# Supply_Sampler.net
KiCad netlist of a schematic drawn in Altium Designer
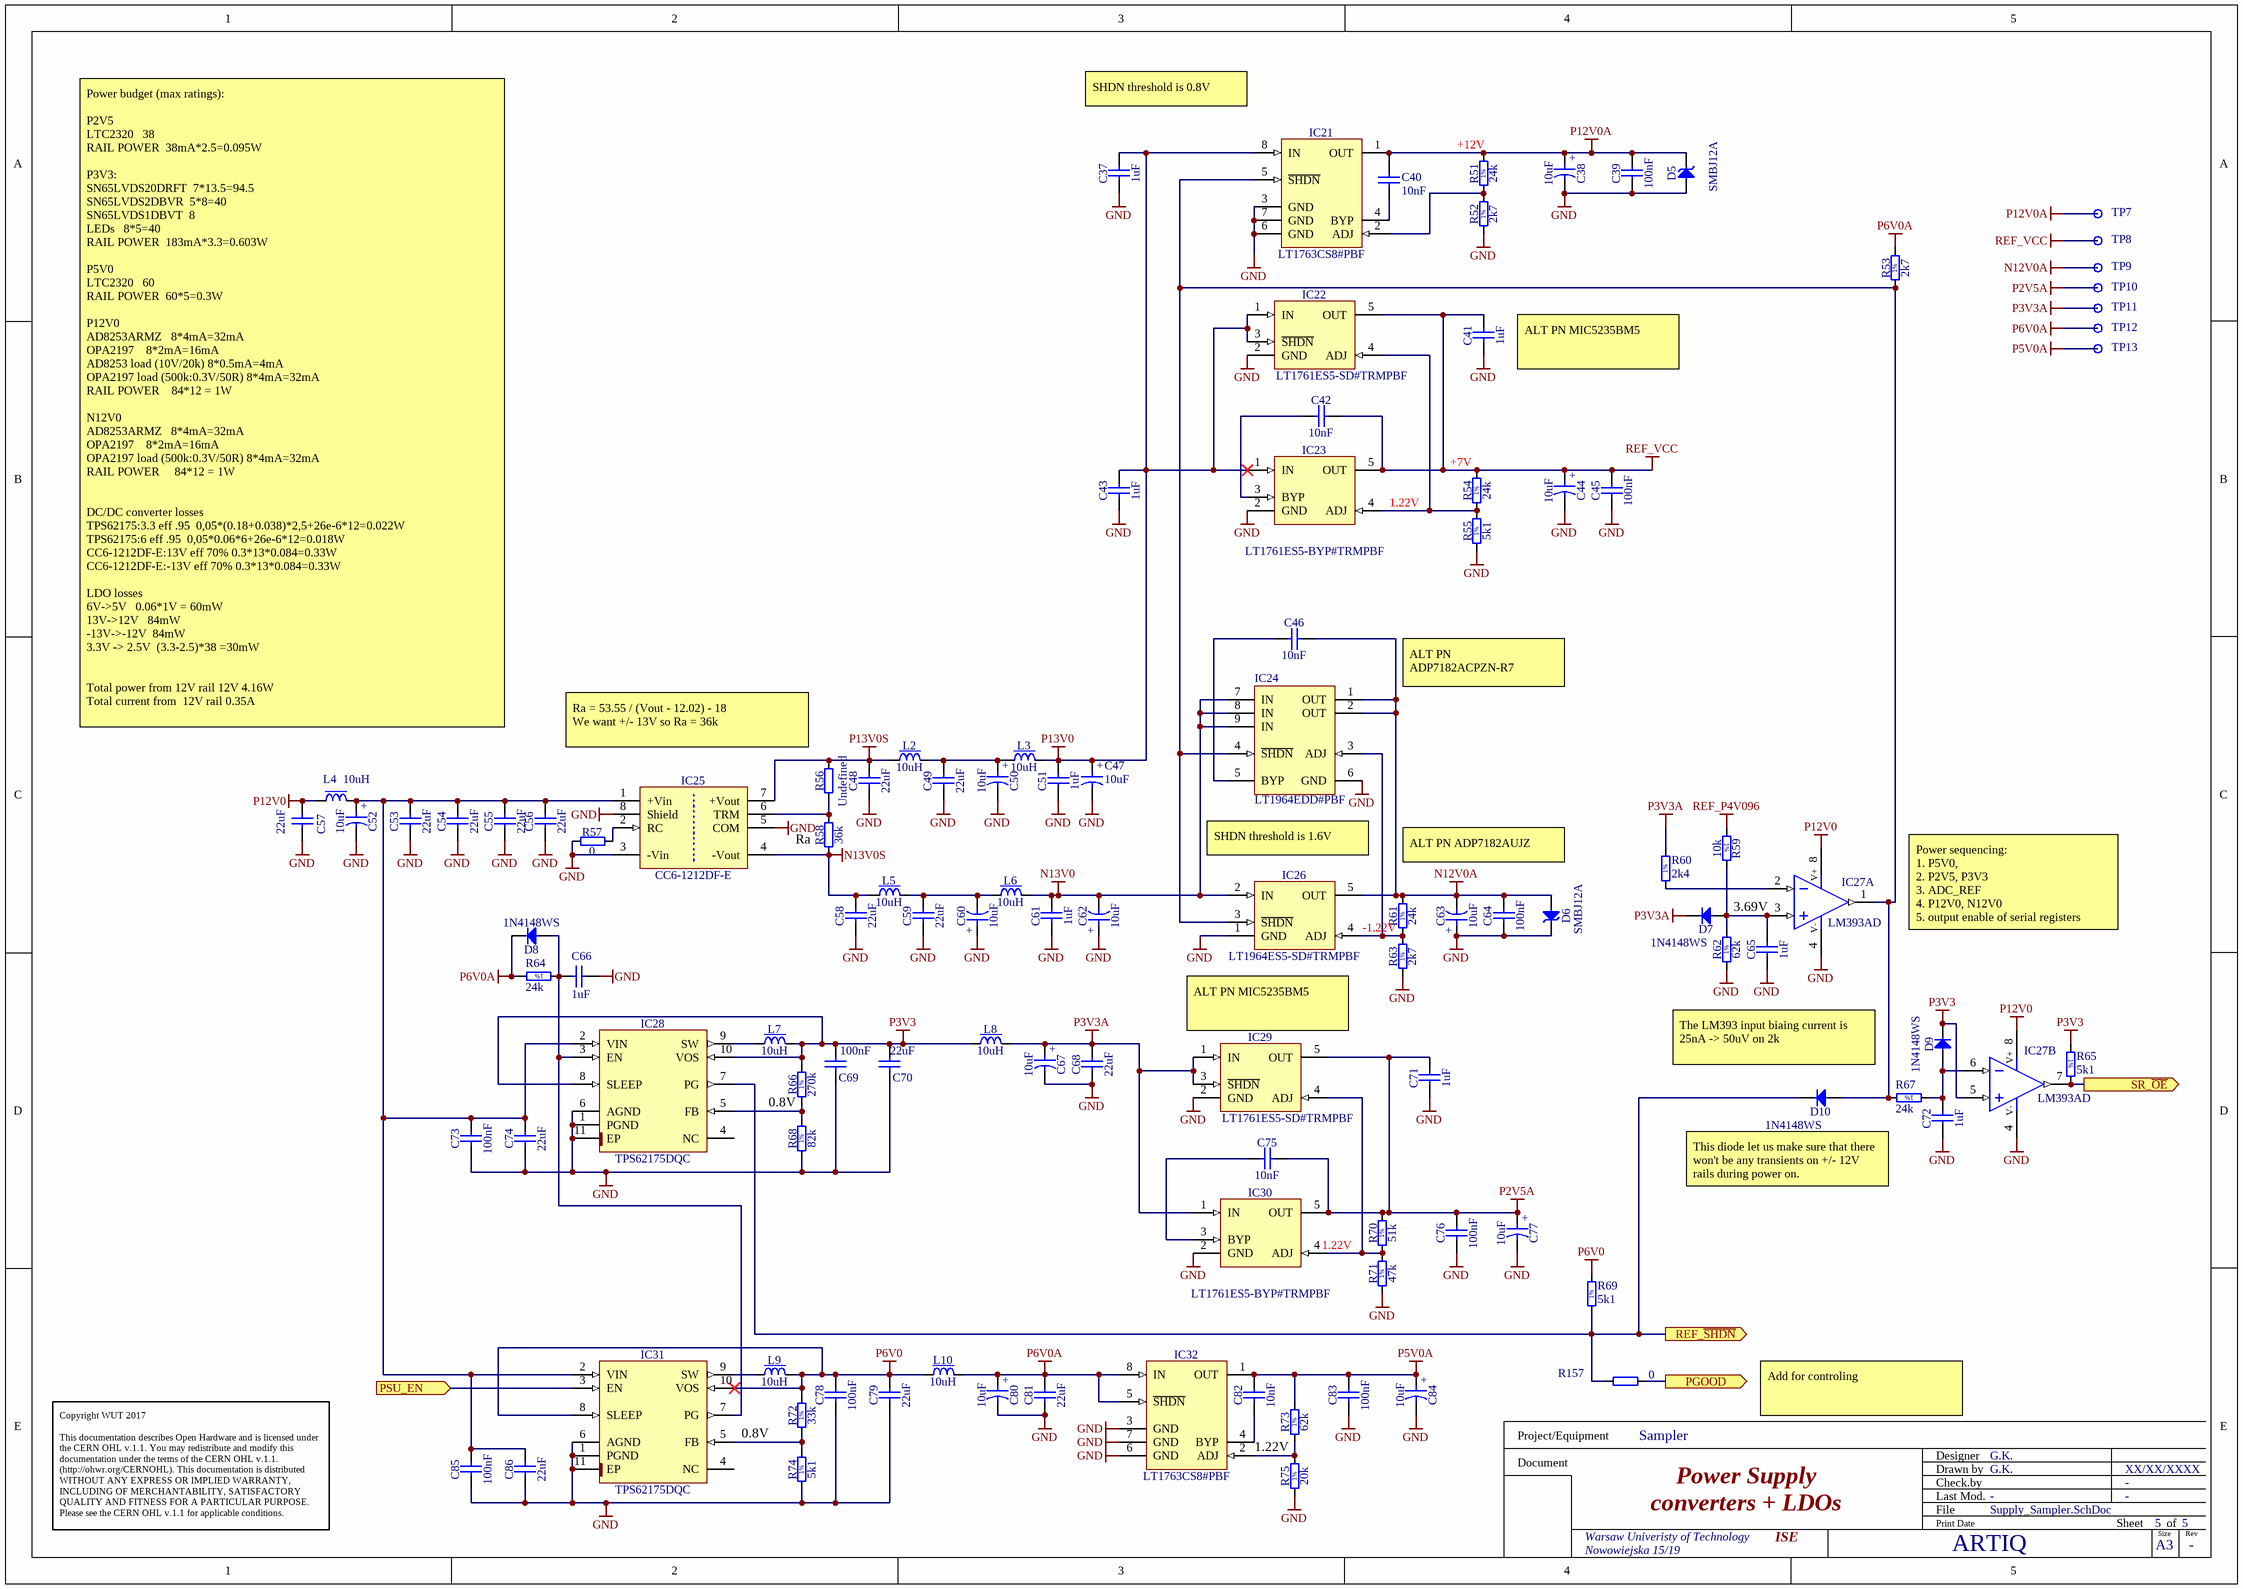
[diagram p0: Supply_Sampler.SchDoc]

(export (version "E")
  (design (tool "Eeschema 10.0.6"))
  (components
    (comp (ref "C37")
      (value "1uF")
      (footprint "CAPC1608X87N")
      (description "Non-polarised capacitor")
      (fields (field (name "PART NUMBER") "CC0603_1UF_25V_10%_X7R") (field (name "VOLTAGE") "25V"))
      (libsource (lib "Capacitors") (part "Capacitor - non polarized"))
    )
    (comp (ref "C38")
      (value "10uF")
      (footprint "CAPMP3216X180N")
      (description "Polarised capacitor")
      (fields (field (name "PART NUMBER") "CTE3216-18_10UF_16V_20%_AVX_TCJ") (field (name "VOLTAGE") "16V"))
      (libsource (lib "Capacitors") (part "Capacitor - polarized"))
    )
    (comp (ref "C39")
      (value "100nF")
      (footprint "CAPC1005X55N")
      (description "Non-polarised capacitor")
      (fields (field (name "PART NUMBER") "CC0402_100NF_16V_10%_X5R") (field (name "VOLTAGE") "16V"))
      (libsource (lib "Capacitors") (part "Capacitor - non polarized"))
    )
    (comp (ref "C40")
      (value "10nF")
      (footprint "CAPC1608X87N")
      (description "Non-polarised capacitor")
      (fields (field (name "PART NUMBER") "CC0603_10NF_50V_10%_X7R") (field (name "VOLTAGE") "50V"))
      (libsource (lib "Capacitors") (part "Capacitor - non polarized"))
    )
    (comp (ref "C41")
      (value "1uF")
      (footprint "CAPC1608X87N")
      (description "Non-polarised capacitor")
      (fields (field (name "PART NUMBER") "CC0603_1UF_25V_10%_X7R") (field (name "VOLTAGE") "25V"))
      (libsource (lib "Capacitors") (part "Capacitor - non polarized"))
    )
    (comp (ref "C42")
      (value "10nF")
      (footprint "CAPC1608X87N")
      (description "Non-polarised capacitor")
      (fields (field (name "PART NUMBER") "CC0603_10NF_50V_10%_X7R") (field (name "VOLTAGE") "50V"))
      (libsource (lib "Capacitors") (part "Capacitor - non polarized"))
    )
    (comp (ref "C43")
      (value "1uF")
      (footprint "CAPC1608X87N")
      (description "Non-polarised capacitor")
      (fields (field (name "PART NUMBER") "CC0603_1UF_25V_10%_X7R") (field (name "VOLTAGE") "25V"))
      (libsource (lib "Capacitors") (part "Capacitor - non polarized"))
    )
    (comp (ref "C44")
      (value "10uF")
      (footprint "CAPMP3216X180N")
      (description "Polarised capacitor")
      (fields (field (name "PART NUMBER") "CTE3216-18_10UF_16V_20%_AVX_TCJ") (field (name "VOLTAGE") "16V"))
      (libsource (lib "Capacitors") (part "Capacitor - polarized"))
    )
    (comp (ref "C45")
      (value "100nF")
      (footprint "CAPC1005X55N")
      (description "Non-polarised capacitor")
      (fields (field (name "PART NUMBER") "CC0402_100NF_16V_10%_X5R") (field (name "VOLTAGE") "16V"))
      (libsource (lib "Capacitors") (part "Capacitor - non polarized"))
    )
    (comp (ref "C46")
      (value "10nF")
      (footprint "CAPC1608X87N")
      (description "Non-polarised capacitor")
      (fields (field (name "PART NUMBER") "CC0603_10NF_50V_10%_X7R") (field (name "VOLTAGE") "50V"))
      (libsource (lib "Capacitors") (part "Capacitor - non polarized"))
    )
    (comp (ref "C47")
      (value "10uF")
      (footprint "CAPMP3216X180N")
      (description "Polarised capacitor")
      (fields (field (name "PART NUMBER") "CTE3216-18_10UF_16V_20%_AVX_TCJ") (field (name "VOLTAGE") "16V"))
      (libsource (lib "Capacitors") (part "Capacitor - polarized"))
    )
    (comp (ref "C48")
      (value "22uF")
      (footprint "CAPC2012X135N")
      (description "Non-polarised capacitor")
      (fields (field (name "PART NUMBER") "CC0805_22UF_16V_10%_X5R") (field (name "VOLTAGE") "16V"))
      (libsource (lib "Capacitors") (part "Capacitor - non polarized"))
    )
    (comp (ref "C49")
      (value "22uF")
      (footprint "CAPC2012X135N")
      (description "Non-polarised capacitor")
      (fields (field (name "PART NUMBER") "CC0805_22UF_16V_10%_X5R") (field (name "VOLTAGE") "16V"))
      (libsource (lib "Capacitors") (part "Capacitor - non polarized"))
    )
    (comp (ref "C50")
      (value "10uF")
      (footprint "CAPMP3216X180N")
      (description "Polarised capacitor")
      (fields (field (name "PART NUMBER") "CTE3216-18_10UF_16V_20%_AVX_TCJ") (field (name "VOLTAGE") "16V"))
      (libsource (lib "Capacitors") (part "Capacitor - polarized"))
    )
    (comp (ref "C51")
      (value "1uF")
      (footprint "CAPC1608X87N")
      (description "Non-polarised capacitor")
      (fields (field (name "PART NUMBER") "CC0603_1UF_25V_10%_X7R") (field (name "VOLTAGE") "25V"))
      (libsource (lib "Capacitors") (part "Capacitor - non polarized"))
    )
    (comp (ref "C52")
      (value "10uF")
      (footprint "CAPMP3216X180N")
      (description "Polarised capacitor")
      (fields (field (name "PART NUMBER") "CTE3216-18_10UF_16V_20%_AVX_TCJ") (field (name "VOLTAGE") "16V"))
      (libsource (lib "Capacitors") (part "Capacitor - polarized"))
    )
    (comp (ref "C53")
      (value "22uF")
      (footprint "CAPC2012X135N")
      (description "Non-polarised capacitor")
      (fields (field (name "PART NUMBER") "CC0805_22UF_16V_10%_X5R") (field (name "VOLTAGE") "16V"))
      (libsource (lib "Capacitors") (part "Capacitor - non polarized"))
    )
    (comp (ref "C54")
      (value "22uF")
      (footprint "CAPC2012X135N")
      (description "Non-polarised capacitor")
      (fields (field (name "PART NUMBER") "CC0805_22UF_16V_10%_X5R") (field (name "VOLTAGE") "16V"))
      (libsource (lib "Capacitors") (part "Capacitor - non polarized"))
    )
    (comp (ref "C55")
      (value "22uF")
      (footprint "CAPC2012X135N")
      (description "Non-polarised capacitor")
      (fields (field (name "PART NUMBER") "CC0805_22UF_16V_10%_X5R") (field (name "VOLTAGE") "16V"))
      (libsource (lib "Capacitors") (part "Capacitor - non polarized"))
    )
    (comp (ref "C56")
      (value "22uF")
      (footprint "CAPC2012X135N")
      (description "Non-polarised capacitor")
      (fields (field (name "PART NUMBER") "CC0805_22UF_16V_10%_X5R") (field (name "VOLTAGE") "16V"))
      (libsource (lib "Capacitors") (part "Capacitor - non polarized"))
    )
    (comp (ref "C57")
      (value "22uF")
      (footprint "CAPC2012X135N")
      (description "Non-polarised capacitor")
      (fields (field (name "PART NUMBER") "CC0805_22UF_16V_10%_X5R") (field (name "VOLTAGE") "16V"))
      (libsource (lib "Capacitors") (part "Capacitor - non polarized"))
    )
    (comp (ref "C58")
      (value "22uF")
      (footprint "CAPC2012X135N")
      (description "Non-polarised capacitor")
      (fields (field (name "PART NUMBER") "CC0805_22UF_16V_10%_X5R") (field (name "VOLTAGE") "16V"))
      (libsource (lib "Capacitors") (part "Capacitor - non polarized"))
    )
    (comp (ref "C59")
      (value "22uF")
      (footprint "CAPC2012X135N")
      (description "Non-polarised capacitor")
      (fields (field (name "PART NUMBER") "CC0805_22UF_16V_10%_X5R") (field (name "VOLTAGE") "16V"))
      (libsource (lib "Capacitors") (part "Capacitor - non polarized"))
    )
    (comp (ref "C60")
      (value "10uF")
      (footprint "CAPMP3216X180N")
      (description "Polarised capacitor")
      (fields (field (name "PART NUMBER") "CTE3216-18_10UF_16V_20%_AVX_TCJ") (field (name "VOLTAGE") "16V"))
      (libsource (lib "Capacitors") (part "Capacitor - polarized"))
    )
    (comp (ref "C61")
      (value "1uF")
      (footprint "CAPC1608X87N")
      (description "Non-polarised capacitor")
      (fields (field (name "PART NUMBER") "CC0603_1UF_25V_10%_X7R") (field (name "VOLTAGE") "25V"))
      (libsource (lib "Capacitors") (part "Capacitor - non polarized"))
    )
    (comp (ref "C62")
      (value "10uF")
      (footprint "CAPMP3216X180N")
      (description "Polarised capacitor")
      (fields (field (name "PART NUMBER") "CTE3216-18_10UF_16V_20%_AVX_TCJ") (field (name "VOLTAGE") "16V"))
      (libsource (lib "Capacitors") (part "Capacitor - polarized"))
    )
    (comp (ref "C63")
      (value "10uF")
      (footprint "CAPMP3216X180N")
      (description "Polarised capacitor")
      (fields (field (name "PART NUMBER") "CTE3216-18_10UF_16V_20%_AVX_TCJ") (field (name "VOLTAGE") "16V"))
      (libsource (lib "Capacitors") (part "Capacitor - polarized"))
    )
    (comp (ref "C64")
      (value "100nF")
      (footprint "CAPC1005X55N")
      (description "Non-polarised capacitor")
      (fields (field (name "PART NUMBER") "CC0402_100NF_16V_10%_X5R") (field (name "VOLTAGE") "16V"))
      (libsource (lib "Capacitors") (part "Capacitor - non polarized"))
    )
    (comp (ref "C65")
      (value "1uF")
      (footprint "CAPC1608X87N")
      (description "Non-polarised capacitor")
      (fields (field (name "PART NUMBER") "CC0603_1UF_25V_10%_X7R") (field (name "VOLTAGE") "25V"))
      (libsource (lib "Capacitors") (part "Capacitor - non polarized"))
    )
    (comp (ref "C66")
      (value "1uF")
      (footprint "CAPC1608X87N")
      (description "Non-polarised capacitor")
      (fields (field (name "PART NUMBER") "CC0603_1UF_25V_10%_X7R") (field (name "VOLTAGE") "25V"))
      (libsource (lib "Capacitors") (part "Capacitor - non polarized"))
    )
    (comp (ref "C67")
      (value "10uF")
      (footprint "CAPMP3216X180N")
      (description "Polarised capacitor")
      (fields (field (name "PART NUMBER") "CTE3216-18_10UF_16V_20%_AVX_TCJ") (field (name "VOLTAGE") "16V"))
      (libsource (lib "Capacitors") (part "Capacitor - polarized"))
    )
    (comp (ref "C68")
      (value "22uF")
      (footprint "CAPC2012X135N")
      (description "Non-polarised capacitor")
      (fields (field (name "PART NUMBER") "CC0805_22UF_16V_10%_X5R") (field (name "VOLTAGE") "16V"))
      (libsource (lib "Capacitors") (part "Capacitor - non polarized"))
    )
    (comp (ref "C69")
      (value "100nF")
      (footprint "CAPC1005X55N")
      (description "Non-polarised capacitor")
      (fields (field (name "PART NUMBER") "CC0402_100NF_16V_10%_X5R") (field (name "VOLTAGE") "16V"))
      (libsource (lib "Capacitors") (part "Capacitor - non polarized"))
    )
    (comp (ref "C70")
      (value "22uF")
      (footprint "CAPC2012X135N")
      (description "Non-polarised capacitor")
      (fields (field (name "PART NUMBER") "CC0805_22UF_16V_10%_X5R") (field (name "VOLTAGE") "16V"))
      (libsource (lib "Capacitors") (part "Capacitor - non polarized"))
    )
    (comp (ref "C71")
      (value "1uF")
      (footprint "CAPC1608X87N")
      (description "Non-polarised capacitor")
      (fields (field (name "PART NUMBER") "CC0603_1UF_25V_10%_X7R") (field (name "VOLTAGE") "25V"))
      (libsource (lib "Capacitors") (part "Capacitor - non polarized"))
    )
    (comp (ref "C72")
      (value "1uF")
      (footprint "CAPC1608X87N")
      (description "Non-polarised capacitor")
      (fields (field (name "PART NUMBER") "CC0603_1UF_25V_10%_X7R") (field (name "VOLTAGE") "25V"))
      (libsource (lib "Capacitors") (part "Capacitor - non polarized"))
    )
    (comp (ref "C73")
      (value "100nF")
      (footprint "CAPC1005X55N")
      (description "Non-polarised capacitor")
      (fields (field (name "PART NUMBER") "CC0402_100NF_16V_10%_X5R") (field (name "VOLTAGE") "16V"))
      (libsource (lib "Capacitors") (part "Capacitor - non polarized"))
    )
    (comp (ref "C74")
      (value "22uF")
      (footprint "CAPC2012X135N")
      (description "Non-polarised capacitor")
      (fields (field (name "PART NUMBER") "CC0805_22UF_16V_10%_X5R") (field (name "VOLTAGE") "16V"))
      (libsource (lib "Capacitors") (part "Capacitor - non polarized"))
    )
    (comp (ref "C75")
      (value "10nF")
      (footprint "CAPC1608X87N")
      (description "Non-polarised capacitor")
      (fields (field (name "PART NUMBER") "CC0603_10NF_50V_10%_X7R") (field (name "VOLTAGE") "50V"))
      (libsource (lib "Capacitors") (part "Capacitor - non polarized"))
    )
    (comp (ref "C76")
      (value "100nF")
      (footprint "CAPC1005X55N")
      (description "Non-polarised capacitor")
      (fields (field (name "PART NUMBER") "CC0402_100NF_16V_10%_X5R") (field (name "VOLTAGE") "16V"))
      (libsource (lib "Capacitors") (part "Capacitor - non polarized"))
    )
    (comp (ref "C77")
      (value "10uF")
      (footprint "CAPMP3216X180N")
      (description "Polarised capacitor")
      (fields (field (name "PART NUMBER") "CTE3216-18_10UF_16V_20%_AVX_TCJ") (field (name "VOLTAGE") "16V"))
      (libsource (lib "Capacitors") (part "Capacitor - polarized"))
    )
    (comp (ref "C78")
      (value "100nF")
      (footprint "CAPC1005X55N")
      (description "Non-polarised capacitor")
      (fields (field (name "PART NUMBER") "CC0402_100NF_16V_10%_X5R") (field (name "VOLTAGE") "16V"))
      (libsource (lib "Capacitors") (part "Capacitor - non polarized"))
    )
    (comp (ref "C79")
      (value "22uF")
      (footprint "CAPC2012X135N")
      (description "Non-polarised capacitor")
      (fields (field (name "PART NUMBER") "CC0805_22UF_16V_10%_X5R") (field (name "VOLTAGE") "16V"))
      (libsource (lib "Capacitors") (part "Capacitor - non polarized"))
    )
    (comp (ref "C80")
      (value "10uF")
      (footprint "CAPMP3216X180N")
      (description "Polarised capacitor")
      (fields (field (name "PART NUMBER") "CTE3216-18_10UF_16V_20%_AVX_TCJ") (field (name "VOLTAGE") "16V"))
      (libsource (lib "Capacitors") (part "Capacitor - polarized"))
    )
    (comp (ref "C81")
      (value "22uF")
      (footprint "CAPC2012X135N")
      (description "Non-polarised capacitor")
      (fields (field (name "PART NUMBER") "CC0805_22UF_16V_10%_X5R") (field (name "VOLTAGE") "16V"))
      (libsource (lib "Capacitors") (part "Capacitor - non polarized"))
    )
    (comp (ref "C82")
      (value "10nF")
      (footprint "CAPC1608X87N")
      (description "Non-polarised capacitor")
      (fields (field (name "PART NUMBER") "CC0603_10NF_50V_10%_X7R") (field (name "VOLTAGE") "50V"))
      (libsource (lib "Capacitors") (part "Capacitor - non polarized"))
    )
    (comp (ref "C83")
      (value "100nF")
      (footprint "CAPC1005X55N")
      (description "Non-polarised capacitor")
      (fields (field (name "PART NUMBER") "CC0402_100NF_16V_10%_X5R") (field (name "VOLTAGE") "16V"))
      (libsource (lib "Capacitors") (part "Capacitor - non polarized"))
    )
    (comp (ref "C84")
      (value "10uF")
      (footprint "CAPMP3216X180N")
      (description "Polarised capacitor")
      (fields (field (name "PART NUMBER") "CTE3216-18_10UF_16V_20%_AVX_TCJ") (field (name "VOLTAGE") "16V"))
      (libsource (lib "Capacitors") (part "Capacitor - polarized"))
    )
    (comp (ref "C85")
      (value "100nF")
      (footprint "CAPC1005X55N")
      (description "Non-polarised capacitor")
      (fields (field (name "PART NUMBER") "CC0402_100NF_16V_10%_X5R") (field (name "VOLTAGE") "16V"))
      (libsource (lib "Capacitors") (part "Capacitor - non polarized"))
    )
    (comp (ref "C86")
      (value "22uF")
      (footprint "CAPC2012X135N")
      (description "Non-polarised capacitor")
      (fields (field (name "PART NUMBER") "CC0805_22UF_16V_10%_X5R") (field (name "VOLTAGE") "16V"))
      (libsource (lib "Capacitors") (part "Capacitor - non polarized"))
    )
    (comp (ref "D5")
      (value "SMBJ12A")
      (footprint "DIOM5336X265N")
      (description "Zener Diode")
      (fields (field (name "VOLTAGE") "12V") (field (name "POWER") "600W"))
      (libsource (lib "ICs And Semiconductors") (part "Diode Zener"))
    )
    (comp (ref "D6")
      (value "SMBJ12A")
      (footprint "DIOM5336X265N")
      (description "Zener Diode")
      (fields (field (name "VOLTAGE") "12V") (field (name "POWER") "600W"))
      (libsource (lib "ICs And Semiconductors") (part "Diode Zener"))
    )
    (comp (ref "D7")
      (value "1N4148WS")
      (footprint "SODFL2512X100N")
      (description "Diode")
      (fields (field (name "VOLTAGE") "75V") (field (name "POWER") "150mA"))
      (libsource (lib "ICs And Semiconductors") (part "Diode"))
    )
    (comp (ref "D8")
      (value "1N4148WS")
      (footprint "SODFL2512X100N")
      (description "Diode")
      (fields (field (name "VOLTAGE") "75V") (field (name "POWER") "150mA"))
      (libsource (lib "ICs And Semiconductors") (part "Diode"))
    )
    (comp (ref "D9")
      (value "1N4148WS")
      (footprint "SODFL2512X100N")
      (description "Diode")
      (fields (field (name "VOLTAGE") "75V") (field (name "POWER") "150mA"))
      (libsource (lib "ICs And Semiconductors") (part "Diode"))
    )
    (comp (ref "D10")
      (value "1N4148WS")
      (footprint "SODFL2512X100N")
      (description "Diode")
      (fields (field (name "VOLTAGE") "75V") (field (name "POWER") "150mA"))
      (libsource (lib "ICs And Semiconductors") (part "Diode"))
    )
    (comp (ref "IC21")
      (value "LT1763CS8#PBF")
      (footprint "SOIC127P600X175-8N")
      (description "1.22V to 20V 500mA, Low Noise, LDO Adjustable Micropower Regulator")
      (fields (field (name "MANUFACTURER") "LINEAR TECHNOLOGY"))
      (libsource (lib "ICs And Semiconductors") (part "LT1763xS8"))
    )
    (comp (ref "IC22")
      (value "LT1761ES5-SD#TRMPBF")
      (footprint "SOT95P280X100-5N")
      (description "100mA, Low Noise, LDO Micropower Adjustable Regulator in SOT-23")
      (fields (field (name "MANUFACTURER") "LINEAR TECHNOLOGY"))
      (libsource (lib "ICs And Semiconductors") (part "LT1761-SD"))
    )
    (comp (ref "IC23")
      (value "LT1761ES5-BYP#TRMPBF")
      (footprint "SOT95P280X100-5N")
      (description "100mA, Low Noise, LDO Micropower Adjustable Regulator in SOT-23")
      (fields (field (name "MANUFACTURER") "LINEAR TECHNOLOGY"))
      (libsource (lib "ICs And Semiconductors") (part "LT1761-BYP"))
    )
    (comp (ref "IC24")
      (value "LT1964EDD#PBF")
      (footprint "LT-DD-8_V")
      (fields (field (name "MANUFACTURER") "Linear Technology"))
      (libsource (lib "Altium Content Vault") (part "LT-LT1964-DD-8"))
    )
    (comp (ref "IC25")
      (value "CC6-1212DF-E")
      (footprint "CC6-1212DF-E")
      (description "CONV DC/DC 6W DUAL 12V +-12V PCB")
      (fields (field (name "MANUFACTURER") "TDK-Lambda Americas Inc."))
      (libsource (lib "Regulators_SMPS") (part "DC/DC_CC6-1212DF-E"))
    )
    (comp (ref "IC26")
      (value "LT1964ES5-SD#TRMPBF")
      (footprint "SOT95P280X100-5N")
      (description "200mA, Low Noise, Low Dropout Negative Micropower Regulator")
      (fields (field (name "MANUFACTURER") "LINEAR TECHNOLOGY"))
      (libsource (lib "ICs And Semiconductors") (part "LT1964-SD"))
    )
    (comp (ref "IC27")
      (value "LM393AD")
      (footprint "SOIC127P600X175-8N")
      (description "Dual Operational Amplifier")
      (fields (field (name "MANUFACTURER") "TEXAS INSTRUMENTS"))
      (libsource (lib "ICs And Semiconductors") (part "Operational Amplifier x2 Type1"))
    )
    (comp (ref "IC28")
      (value "TPS62175DQC")
      (footprint "SON50P200X300X80-11N-R94X250")
      (description "4.75-28VDC to 1-6VDC, 500mA Step-Down Converter With Sleep Mode")
      (fields (field (name "MANUFACTURER") "TEXAS INSTRUMENTS"))
      (libsource (lib "ICs And Semiconductors") (part "TPS62175"))
    )
    (comp (ref "IC29")
      (value "LT1761ES5-SD#TRMPBF")
      (footprint "SOT95P280X100-5N")
      (description "100mA, Low Noise, LDO Micropower Adjustable Regulator in SOT-23")
      (fields (field (name "MANUFACTURER") "LINEAR TECHNOLOGY"))
      (libsource (lib "ICs And Semiconductors") (part "LT1761-SD"))
    )
    (comp (ref "IC30")
      (value "LT1761ES5-BYP#TRMPBF")
      (footprint "SOT95P280X100-5N")
      (description "100mA, Low Noise, LDO Micropower Adjustable Regulator in SOT-23")
      (fields (field (name "MANUFACTURER") "LINEAR TECHNOLOGY"))
      (libsource (lib "ICs And Semiconductors") (part "LT1761-BYP"))
    )
    (comp (ref "IC31")
      (value "TPS62175DQC")
      (footprint "SON50P200X300X80-11N-R94X250")
      (description "4.75-28VDC to 1-6VDC, 500mA Step-Down Converter With Sleep Mode")
      (fields (field (name "MANUFACTURER") "TEXAS INSTRUMENTS"))
      (libsource (lib "ICs And Semiconductors") (part "TPS62175"))
    )
    (comp (ref "IC32")
      (value "LT1763CS8#PBF")
      (footprint "SOIC127P600X175-8N")
      (description "1.22V to 20V 500mA, Low Noise, LDO Adjustable Micropower Regulator")
      (fields (field (name "MANUFACTURER") "LINEAR TECHNOLOGY"))
      (libsource (lib "ICs And Semiconductors") (part "LT1763xS8"))
    )
    (comp (ref "L2")
      (value "10uH")
      (footprint "IND_MURATA-PS_8400")
      (description "Inductor With Core")
      (fields (field (name "PART NUMBER") "IND_10UH_10%_MURATA-PS_8400") (field (name "POWER") "950mA"))
      (libsource (lib "Inductors & Transformers") (part "Inductor With Magnetic core"))
    )
    (comp (ref "L3")
      (value "10uH")
      (footprint "IND_MURATA-PS_8400")
      (description "Inductor With Core")
      (fields (field (name "PART NUMBER") "IND_10UH_10%_MURATA-PS_8400") (field (name "POWER") "950mA"))
      (libsource (lib "Inductors & Transformers") (part "Inductor With Magnetic core"))
    )
    (comp (ref "L4")
      (value "10uH")
      (footprint "IND_MURATA-PS_8400")
      (description "Inductor With Core")
      (fields (field (name "PART NUMBER") "IND_10UH_10%_MURATA-PS_8400") (field (name "POWER") "950mA"))
      (libsource (lib "Inductors & Transformers") (part "Inductor With Magnetic core"))
    )
    (comp (ref "L5")
      (value "10uH")
      (footprint "IND_MURATA-PS_8400")
      (description "Inductor With Core")
      (fields (field (name "PART NUMBER") "IND_10UH_10%_MURATA-PS_8400") (field (name "POWER") "950mA"))
      (libsource (lib "Inductors & Transformers") (part "Inductor With Magnetic core"))
    )
    (comp (ref "L6")
      (value "10uH")
      (footprint "IND_MURATA-PS_8400")
      (description "Inductor With Core")
      (fields (field (name "PART NUMBER") "IND_10UH_10%_MURATA-PS_8400") (field (name "POWER") "950mA"))
      (libsource (lib "Inductors & Transformers") (part "Inductor With Magnetic core"))
    )
    (comp (ref "L7")
      (value "10uH")
      (footprint "IND_MURATA-PS_8400")
      (description "Inductor With Core")
      (fields (field (name "PART NUMBER") "IND_10UH_10%_MURATA-PS_8400") (field (name "POWER") "950mA"))
      (libsource (lib "Inductors & Transformers") (part "Inductor With Magnetic core"))
    )
    (comp (ref "L8")
      (value "10uH")
      (footprint "IND_MURATA-PS_8400")
      (description "Inductor With Core")
      (fields (field (name "PART NUMBER") "IND_10UH_10%_MURATA-PS_8400") (field (name "POWER") "950mA"))
      (libsource (lib "Inductors & Transformers") (part "Inductor With Magnetic core"))
    )
    (comp (ref "L9")
      (value "10uH")
      (footprint "IND_MURATA-PS_8400")
      (description "Inductor With Core")
      (fields (field (name "PART NUMBER") "IND_10UH_10%_MURATA-PS_8400") (field (name "POWER") "950mA"))
      (libsource (lib "Inductors & Transformers") (part "Inductor With Magnetic core"))
    )
    (comp (ref "L10")
      (value "10uH")
      (footprint "IND_MURATA-PS_8400")
      (description "Inductor With Core")
      (fields (field (name "PART NUMBER") "IND_10UH_10%_MURATA-PS_8400") (field (name "POWER") "950mA"))
      (libsource (lib "Inductors & Transformers") (part "Inductor With Magnetic core"))
    )
    (comp (ref "R51")
      (value "24k")
      (footprint "RESC1608X55N")
      (description "Resistor - 1%")
      (fields (field (name "PART NUMBER") "R0603_24K_1%_0.1W_100PPM") (field (name "POWER") "0.1W"))
      (libsource (lib "Resistors") (part "Resistor - 1%"))
    )
    (comp (ref "R52")
      (value "2k7")
      (footprint "RESC1608X55N")
      (description "Resistor - 1%")
      (fields (field (name "PART NUMBER") "R0603_2K7_1%_0.1W_100PPM") (field (name "POWER") "0.1W"))
      (libsource (lib "Resistors") (part "Resistor - 1%"))
    )
    (comp (ref "R53")
      (value "2k7")
      (footprint "RESC1608X55N")
      (description "Resistor - 1%")
      (fields (field (name "PART NUMBER") "R0603_2K7_1%_0.1W_100PPM") (field (name "POWER") "0.1W"))
      (libsource (lib "Resistors") (part "Resistor - 1%"))
    )
    (comp (ref "R54")
      (value "24k")
      (footprint "RESC1608X55N")
      (description "Resistor - 1%")
      (fields (field (name "PART NUMBER") "R0603_24K_1%_0.1W_100PPM") (field (name "POWER") "0.1W"))
      (libsource (lib "Resistors") (part "Resistor - 1%"))
    )
    (comp (ref "R55")
      (value "5k1")
      (footprint "RESC1005X40N")
      (description "Resistor - 1%")
      (fields (field (name "PART NUMBER") "R0402_5K1_1%_0.0625W_100PPM") (field (name "POWER") "0.0625W"))
      (libsource (lib "Resistors") (part "Resistor - 1%"))
    )
    (comp (ref "R56")
      (value "Undefined")
      (footprint "RESC1608X55N")
      (description "Resistor")
      (fields (field (name "PART NUMBER") "R0603_NO-VALUE"))
      (libsource (lib "Resistors") (part "Resistor"))
    )
    (comp (ref "R57")
      (value "0")
      (footprint "RESC1005X40N")
      (description "Resistor")
      (fields (field (name "PART NUMBER") "R0402_0R_JUMPER") (field (name "MANUFACTURER") "GENERIC"))
      (libsource (lib "Resistors") (part "Resistor"))
    )
    (comp (ref "R58")
      (value "36k")
      (footprint "RESC1608X55N")
      (description "Resistor - 1%")
      (fields (field (name "PART NUMBER") "R0603_36K_1%_0.1W_100PPM") (field (name "POWER") "0.1W"))
      (libsource (lib "") (part "Resistor - 1%_1"))
    )
    (comp (ref "R59")
      (value "10k")
      (footprint "RESC1005X40N")
      (description "Resistor - 1%")
      (fields (field (name "PART NUMBER") "R0402_10K_1%_0.0625W_100PPM") (field (name "POWER") "0.0625W"))
      (libsource (lib "Resistors") (part "Resistor - 1%"))
    )
    (comp (ref "R60")
      (value "2k4")
      (footprint "RESC1005X40N")
      (description "Resistor - 1%")
      (fields (field (name "PART NUMBER") "R0402_2K4_1%_0.0625W_100PPM") (field (name "POWER") "0.0625W"))
      (libsource (lib "Resistors") (part "Resistor - 1%"))
    )
    (comp (ref "R61")
      (value "24k")
      (footprint "RESC1608X55N")
      (description "Resistor - 1%")
      (fields (field (name "PART NUMBER") "R0603_24K_1%_0.1W_100PPM") (field (name "POWER") "0.1W"))
      (libsource (lib "Resistors") (part "Resistor - 1%"))
    )
    (comp (ref "R62")
      (value "62k")
      (footprint "RESC1005X40N")
      (description "Resistor - 1%")
      (fields (field (name "PART NUMBER") "R0402_62K_1%_0.0625W_100PPM") (field (name "POWER") "0.0625W"))
      (libsource (lib "Resistors") (part "Resistor - 1%"))
    )
    (comp (ref "R63")
      (value "2k7")
      (footprint "RESC1608X55N")
      (description "Resistor - 1%")
      (fields (field (name "PART NUMBER") "R0603_2K7_1%_0.1W_100PPM") (field (name "POWER") "0.1W"))
      (libsource (lib "Resistors") (part "Resistor - 1%"))
    )
    (comp (ref "R64")
      (value "24k")
      (footprint "RESC1608X55N")
      (description "Resistor - 1%")
      (fields (field (name "PART NUMBER") "R0603_24K_1%_0.1W_100PPM") (field (name "POWER") "0.1W"))
      (libsource (lib "Resistors") (part "Resistor - 1%"))
    )
    (comp (ref "R65")
      (value "5k1")
      (footprint "RESC1005X40N")
      (description "Resistor - 1%")
      (fields (field (name "PART NUMBER") "R0402_5K1_1%_0.0625W_100PPM") (field (name "POWER") "0.0625W"))
      (libsource (lib "Resistors") (part "Resistor - 1%"))
    )
    (comp (ref "R66")
      (value "270k")
      (footprint "RESC1608X55N")
      (description "Resistor - 1%")
      (fields (field (name "PART NUMBER") "R0603_270K_1%_0.1W_100PPM") (field (name "POWER") "0.1W"))
      (libsource (lib "Resistors") (part "Resistor - 1%"))
    )
    (comp (ref "R67")
      (value "24k")
      (footprint "RESC1608X55N")
      (description "Resistor - 1%")
      (fields (field (name "PART NUMBER") "R0603_24K_1%_0.1W_100PPM") (field (name "POWER") "0.1W"))
      (libsource (lib "Resistors") (part "Resistor - 1%"))
    )
    (comp (ref "R68")
      (value "82k")
      (footprint "RESC1608X55N")
      (description "Resistor - 1%")
      (fields (field (name "PART NUMBER") "R0603_82K_1%_0.1W_100PPM") (field (name "POWER") "0.1W"))
      (libsource (lib "Resistors") (part "Resistor - 1%"))
    )
    (comp (ref "R69")
      (value "5k1")
      (footprint "RESC1005X40N")
      (description "Resistor - 1%")
      (fields (field (name "PART NUMBER") "R0402_5K1_1%_0.0625W_100PPM") (field (name "POWER") "0.0625W"))
      (libsource (lib "Resistors") (part "Resistor - 1%"))
    )
    (comp (ref "R70")
      (value "51k")
      (footprint "RESC1005X40N")
      (description "Resistor - 1%")
      (fields (field (name "PART NUMBER") "R0402_51K_1%_0.0625W_100PPM") (field (name "POWER") "0.0625W"))
      (libsource (lib "Resistors") (part "Resistor - 1%"))
    )
    (comp (ref "R71")
      (value "47k")
      (footprint "RESC1005X40N")
      (description "Resistor - 1%")
      (fields (field (name "PART NUMBER") "R0402_47K_1%_0.0625W_100PPM") (field (name "POWER") "0.0625W"))
      (libsource (lib "Resistors") (part "Resistor - 1%"))
    )
    (comp (ref "R72")
      (value "33k")
      (footprint "RESC1005X40N")
      (description "Resistor - 1%")
      (fields (field (name "PART NUMBER") "R0402_33K_1%_0.0625W_100PPM") (field (name "POWER") "0.0625W"))
      (libsource (lib "Resistors") (part "Resistor - 1%"))
    )
    (comp (ref "R73")
      (value "62k")
      (footprint "RESC1005X40N")
      (description "Resistor - 1%")
      (fields (field (name "PART NUMBER") "R0402_62K_1%_0.0625W_100PPM") (field (name "POWER") "0.0625W"))
      (libsource (lib "Resistors") (part "Resistor - 1%"))
    )
    (comp (ref "R74")
      (value "5k1")
      (footprint "RESC1005X40N")
      (description "Resistor - 1%")
      (fields (field (name "PART NUMBER") "R0402_5K1_1%_0.0625W_100PPM") (field (name "POWER") "0.0625W"))
      (libsource (lib "Resistors") (part "Resistor - 1%"))
    )
    (comp (ref "R75")
      (value "20k")
      (footprint "RESC1005X40N")
      (description "Resistor - 1%")
      (fields (field (name "PART NUMBER") "R0402_20K_1%_0.0625W_100PPM") (field (name "POWER") "0.0625W"))
      (libsource (lib "Resistors") (part "Resistor - 1%"))
    )
    (comp (ref "R157")
      (value "0")
      (footprint "RESC1005X40N")
      (description "Resistor")
      (fields (field (name "PART NUMBER") "R0402_0R_JUMPER") (field (name "MANUFACTURER") "GENERIC"))
      (libsource (lib "Resistors") (part "Resistor"))
    )
    (comp (ref "TP7")
      (value "Test Point")
      (footprint "TPS127")
      (fields (field (name "PART NUMBER") "SMD_PAD_1.27X1.27MM"))
      (libsource (lib "Eletro-mechanical") (part "Test Point"))
    )
    (comp (ref "TP8")
      (value "Test Point")
      (footprint "TPS127")
      (fields (field (name "PART NUMBER") "SMD_PAD_1.27X1.27MM"))
      (libsource (lib "Eletro-mechanical") (part "Test Point"))
    )
    (comp (ref "TP9")
      (value "Test Point")
      (footprint "TPS127")
      (fields (field (name "PART NUMBER") "SMD_PAD_1.27X1.27MM"))
      (libsource (lib "Eletro-mechanical") (part "Test Point"))
    )
    (comp (ref "TP10")
      (value "Test Point")
      (footprint "TPS127")
      (fields (field (name "PART NUMBER") "SMD_PAD_1.27X1.27MM"))
      (libsource (lib "Eletro-mechanical") (part "Test Point"))
    )
    (comp (ref "TP11")
      (value "Test Point")
      (footprint "TPS127")
      (fields (field (name "PART NUMBER") "SMD_PAD_1.27X1.27MM"))
      (libsource (lib "Eletro-mechanical") (part "Test Point"))
    )
    (comp (ref "TP12")
      (value "Test Point")
      (footprint "TPS127")
      (fields (field (name "PART NUMBER") "SMD_PAD_1.27X1.27MM"))
      (libsource (lib "Eletro-mechanical") (part "Test Point"))
    )
    (comp (ref "TP13")
      (value "Test Point")
      (footprint "TPS127")
      (fields (field (name "PART NUMBER") "SMD_PAD_1.27X1.27MM"))
      (libsource (lib "Eletro-mechanical") (part "Test Point"))
    )
  )
  (nets
    (net (code "1") (name "/PGOOD") (class "Default")
      (node (ref "R157") (pin "2") (pinfunction "2_2") (pintype "passive"))
    )
    (net (code "2") (name "/PSU_EN") (class "Default")
      (node (ref "IC31") (pin "3") (pinfunction "EN_3") (pintype "input"))
    )
    (net (code "3") (name "/REF_~{SHDN}") (class "Default")
      (node (ref "D10") (pin "1") (pinfunction "C_1") (pintype "passive"))
      (node (ref "IC28") (pin "7") (pinfunction "PG_7") (pintype "output"))
      (node (ref "R157") (pin "1") (pinfunction "1_1") (pintype "passive"))
      (node (ref "R69") (pin "1") (pinfunction "1_1") (pintype "passive"))
    )
    (net (code "4") (name "/SR_~{OE}") (class "Default")
      (node (ref "IC27") (pin "7") (pinfunction "OUT_7") (pintype "output"))
      (node (ref "R65") (pin "2") (pinfunction "2_2") (pintype "passive"))
    )
    (net (code "5") (name "GND") (class "Default")
      (node (ref "C37") (pin "1") (pinfunction "1_1") (pintype "passive"))
      (node (ref "C38") (pin "2") (pinfunction "2_2") (pintype "passive"))
      (node (ref "C39") (pin "1") (pinfunction "1_1") (pintype "passive"))
      (node (ref "C41") (pin "1") (pinfunction "1_1") (pintype "passive"))
      (node (ref "C43") (pin "1") (pinfunction "1_1") (pintype "passive"))
      (node (ref "C44") (pin "2") (pinfunction "2_2") (pintype "passive"))
      (node (ref "C45") (pin "1") (pinfunction "1_1") (pintype "passive"))
      (node (ref "C47") (pin "2") (pinfunction "2_2") (pintype "passive"))
      (node (ref "C48") (pin "1") (pinfunction "1_1") (pintype "passive"))
      (node (ref "C49") (pin "1") (pinfunction "1_1") (pintype "passive"))
      (node (ref "C50") (pin "2") (pinfunction "2_2") (pintype "passive"))
      (node (ref "C51") (pin "1") (pinfunction "1_1") (pintype "passive"))
      (node (ref "C52") (pin "2") (pinfunction "2_2") (pintype "passive"))
      (node (ref "C53") (pin "1") (pinfunction "1_1") (pintype "passive"))
      (node (ref "C54") (pin "1") (pinfunction "1_1") (pintype "passive"))
      (node (ref "C55") (pin "1") (pinfunction "1_1") (pintype "passive"))
      (node (ref "C56") (pin "1") (pinfunction "1_1") (pintype "passive"))
      (node (ref "C57") (pin "1") (pinfunction "1_1") (pintype "passive"))
      (node (ref "C58") (pin "1") (pinfunction "1_1") (pintype "passive"))
      (node (ref "C59") (pin "1") (pinfunction "1_1") (pintype "passive"))
      (node (ref "C60") (pin "1") (pinfunction "1_1") (pintype "passive"))
      (node (ref "C61") (pin "1") (pinfunction "1_1") (pintype "passive"))
      (node (ref "C62") (pin "1") (pinfunction "1_1") (pintype "passive"))
      (node (ref "C63") (pin "1") (pinfunction "1_1") (pintype "passive"))
      (node (ref "C64") (pin "1") (pinfunction "1_1") (pintype "passive"))
      (node (ref "C65") (pin "1") (pinfunction "1_1") (pintype "passive"))
      (node (ref "C66") (pin "1") (pinfunction "1_1") (pintype "passive"))
      (node (ref "C67") (pin "2") (pinfunction "2_2") (pintype "passive"))
      (node (ref "C68") (pin "1") (pinfunction "1_1") (pintype "passive"))
      (node (ref "C69") (pin "1") (pinfunction "1_1") (pintype "passive"))
      (node (ref "C70") (pin "1") (pinfunction "1_1") (pintype "passive"))
      (node (ref "C71") (pin "1") (pinfunction "1_1") (pintype "passive"))
      (node (ref "C72") (pin "1") (pinfunction "1_1") (pintype "passive"))
      (node (ref "C73") (pin "1") (pinfunction "1_1") (pintype "passive"))
      (node (ref "C74") (pin "1") (pinfunction "1_1") (pintype "passive"))
      (node (ref "C76") (pin "1") (pinfunction "1_1") (pintype "passive"))
      (node (ref "C77") (pin "2") (pinfunction "2_2") (pintype "passive"))
      (node (ref "C78") (pin "1") (pinfunction "1_1") (pintype "passive"))
      (node (ref "C79") (pin "1") (pinfunction "1_1") (pintype "passive"))
      (node (ref "C80") (pin "2") (pinfunction "2_2") (pintype "passive"))
      (node (ref "C81") (pin "1") (pinfunction "1_1") (pintype "passive"))
      (node (ref "C83") (pin "1") (pinfunction "1_1") (pintype "passive"))
      (node (ref "C84") (pin "2") (pinfunction "2_2") (pintype "passive"))
      (node (ref "C85") (pin "1") (pinfunction "1_1") (pintype "passive"))
      (node (ref "C86") (pin "1") (pinfunction "1_1") (pintype "passive"))
      (node (ref "D5") (pin "2") (pinfunction "A_2") (pintype "passive"))
      (node (ref "D6") (pin "1") (pinfunction "C_1") (pintype "passive"))
      (node (ref "IC21") (pin "3") (pinfunction "GND_3") (pintype "power_in"))
      (node (ref "IC21") (pin "6") (pinfunction "GND_6") (pintype "power_in"))
      (node (ref "IC21") (pin "7") (pinfunction "GND_7") (pintype "power_in"))
      (node (ref "IC22") (pin "2") (pinfunction "GND_2") (pintype "power_in"))
      (node (ref "IC23") (pin "2") (pinfunction "GND_2") (pintype "power_in"))
      (node (ref "IC24") (pin "6") (pinfunction "GND_6") (pintype "power_in"))
      (node (ref "IC25") (pin "3") (pinfunction "-Vin_3") (pintype "power_in"))
      (node (ref "IC25") (pin "5") (pinfunction "COM_5") (pintype "power_in"))
      (node (ref "IC25") (pin "8") (pinfunction "Shield_8") (pintype "power_in"))
      (node (ref "IC26") (pin "1") (pinfunction "GND_1") (pintype "power_in"))
      (node (ref "IC27") (pin "4") (pinfunction "V-_4") (pintype "power_in"))
      (node (ref "IC28") (pin "1") (pinfunction "PGND_1") (pintype "power_in"))
      (node (ref "IC28") (pin "11") (pinfunction "EP_11") (pintype "power_in"))
      (node (ref "IC28") (pin "6") (pinfunction "AGND_6") (pintype "power_in"))
      (node (ref "IC29") (pin "2") (pinfunction "GND_2") (pintype "power_in"))
      (node (ref "IC30") (pin "2") (pinfunction "GND_2") (pintype "power_in"))
      (node (ref "IC31") (pin "1") (pinfunction "PGND_1") (pintype "power_in"))
      (node (ref "IC31") (pin "11") (pinfunction "EP_11") (pintype "power_in"))
      (node (ref "IC31") (pin "6") (pinfunction "AGND_6") (pintype "power_in"))
      (node (ref "IC32") (pin "3") (pinfunction "GND_3") (pintype "power_in"))
      (node (ref "IC32") (pin "6") (pinfunction "GND_6") (pintype "power_in"))
      (node (ref "IC32") (pin "7") (pinfunction "GND_7") (pintype "power_in"))
      (node (ref "R52") (pin "1") (pinfunction "1_1") (pintype "passive"))
      (node (ref "R55") (pin "1") (pinfunction "1_1") (pintype "passive"))
      (node (ref "R57") (pin "1") (pinfunction "1_1") (pintype "passive"))
      (node (ref "R62") (pin "1") (pinfunction "1_1") (pintype "passive"))
      (node (ref "R63") (pin "1") (pinfunction "1_1") (pintype "passive"))
      (node (ref "R68") (pin "1") (pinfunction "1_1") (pintype "passive"))
      (node (ref "R71") (pin "1") (pinfunction "1_1") (pintype "passive"))
      (node (ref "R74") (pin "1") (pinfunction "1_1") (pintype "passive"))
      (node (ref "R75") (pin "1") (pinfunction "1_1") (pintype "passive"))
    )
    (net (code "6") (name "N12V0A") (class "Default")
      (node (ref "C46") (pin "2") (pinfunction "2_2") (pintype "passive"))
      (node (ref "C63") (pin "2") (pinfunction "2_2") (pintype "passive"))
      (node (ref "C64") (pin "2") (pinfunction "2_2") (pintype "passive"))
      (node (ref "D6") (pin "2") (pinfunction "A_2") (pintype "passive"))
      (node (ref "IC24") (pin "1") (pinfunction "OUT_1") (pintype "power_in"))
      (node (ref "IC24") (pin "2") (pinfunction "OUT_2") (pintype "power_in"))
      (node (ref "IC26") (pin "5") (pinfunction "OUT_5") (pintype "power_in"))
      (node (ref "R61") (pin "2") (pinfunction "2_2") (pintype "passive"))
      (node (ref "TP9") (pin "1") (pinfunction "1_1") (pintype "bidirectional"))
    )
    (net (code "7") (name "N13V0") (class "Default")
      (node (ref "C61") (pin "2") (pinfunction "2_2") (pintype "passive"))
      (node (ref "C62") (pin "2") (pinfunction "2_2") (pintype "passive"))
      (node (ref "IC24") (pin "7") (pinfunction "IN_7") (pintype "power_in"))
      (node (ref "IC24") (pin "8") (pinfunction "IN_8") (pintype "power_in"))
      (node (ref "IC24") (pin "9") (pinfunction "IN_9") (pintype "power_in"))
      (node (ref "IC26") (pin "2") (pinfunction "IN_2") (pintype "input"))
      (node (ref "L6") (pin "2") (pinfunction "2_2") (pintype "passive"))
    )
    (net (code "8") (name "N13V0S") (class "Default")
      (node (ref "C58") (pin "2") (pinfunction "2_2") (pintype "passive"))
      (node (ref "IC25") (pin "4") (pinfunction "-Vout_4") (pintype "power_in"))
      (node (ref "L5") (pin "1") (pinfunction "1_1") (pintype "passive"))
      (node (ref "R58") (pin "1") (pinfunction "1_1") (pintype "passive"))
    )
    (net (code "9") (name "Net-(C49-Pad2)") (class "Default")
      (node (ref "C49") (pin "2") (pinfunction "2_2") (pintype "passive"))
      (node (ref "C50") (pin "1") (pinfunction "1_1") (pintype "passive"))
      (node (ref "L2") (pin "2") (pinfunction "2_2") (pintype "passive"))
      (node (ref "L3") (pin "1") (pinfunction "1_1") (pintype "passive"))
    )
    (net (code "10") (name "Net-(C59-Pad2)") (class "Default")
      (node (ref "C59") (pin "2") (pinfunction "2_2") (pintype "passive"))
      (node (ref "C60") (pin "2") (pinfunction "2_2") (pintype "passive"))
      (node (ref "L5") (pin "2") (pinfunction "2_2") (pintype "passive"))
      (node (ref "L6") (pin "1") (pinfunction "1_1") (pintype "passive"))
    )
    (net (code "11") (name "Net-(D7-A)") (class "Default")
      (node (ref "C65") (pin "2") (pinfunction "2_2") (pintype "passive"))
      (node (ref "D7") (pin "2") (pinfunction "A_2") (pintype "passive"))
      (node (ref "IC27") (pin "3") (pinfunction "IN+_3") (pintype "input"))
      (node (ref "R59") (pin "2") (pinfunction "2_2") (pintype "passive"))
      (node (ref "R62") (pin "2") (pinfunction "2_2") (pintype "passive"))
    )
    (net (code "12") (name "Net-(D8-A)") (class "Default")
      (node (ref "C66") (pin "2") (pinfunction "2_2") (pintype "passive"))
      (node (ref "D8") (pin "2") (pinfunction "A_2") (pintype "passive"))
      (node (ref "IC28") (pin "3") (pinfunction "EN_3") (pintype "input"))
      (node (ref "IC31") (pin "7") (pinfunction "PG_7") (pintype "output"))
      (node (ref "R64") (pin "1") (pinfunction "1_1") (pintype "passive"))
    )
    (net (code "13") (name "Net-(D9-A)") (class "Default")
      (node (ref "C72") (pin "2") (pinfunction "2_2") (pintype "passive"))
      (node (ref "D9") (pin "2") (pinfunction "A_2") (pintype "passive"))
      (node (ref "IC27") (pin "6") (pinfunction "IN-_6") (pintype "input"))
      (node (ref "R67") (pin "1") (pinfunction "1_1") (pintype "passive"))
    )
    (net (code "14") (name "Net-(D10-A)") (class "Default")
      (node (ref "D10") (pin "2") (pinfunction "A_2") (pintype "passive"))
      (node (ref "IC21") (pin "5") (pinfunction "~{SHDN}_5") (pintype "input"))
      (node (ref "IC24") (pin "4") (pinfunction "~{SHDN}_4") (pintype "input"))
      (node (ref "IC26") (pin "3") (pinfunction "~{SHDN}_3") (pintype "input"))
      (node (ref "IC27") (pin "1") (pinfunction "OUT_1") (pintype "output"))
      (node (ref "R53") (pin "1") (pinfunction "1_1") (pintype "passive"))
      (node (ref "R67") (pin "2") (pinfunction "2_2") (pintype "passive"))
    )
    (net (code "15") (name "Net-(IC21-ADJ)") (class "Default")
      (node (ref "IC21") (pin "2") (pinfunction "ADJ_2") (pintype "input"))
      (node (ref "R51") (pin "1") (pinfunction "1_1") (pintype "passive"))
      (node (ref "R52") (pin "2") (pinfunction "2_2") (pintype "passive"))
    )
    (net (code "16") (name "Net-(IC21-BYP)") (class "Default")
      (node (ref "C40") (pin "1") (pinfunction "1_1") (pintype "passive"))
      (node (ref "IC21") (pin "4") (pinfunction "BYP_4") (pintype "passive"))
    )
    (net (code "17") (name "Net-(IC22-ADJ)") (class "Default")
      (node (ref "IC22") (pin "4") (pinfunction "ADJ_4") (pintype "input"))
      (node (ref "IC23") (pin "4") (pinfunction "ADJ_4") (pintype "input"))
      (node (ref "R54") (pin "1") (pinfunction "1_1") (pintype "passive"))
      (node (ref "R55") (pin "2") (pinfunction "2_2") (pintype "passive"))
    )
    (net (code "18") (name "Net-(IC23-BYP)") (class "Default")
      (node (ref "C42") (pin "1") (pinfunction "1_1") (pintype "passive"))
      (node (ref "IC23") (pin "3") (pinfunction "BYP_3") (pintype "input"))
    )
    (net (code "19") (name "Net-(IC24-ADJ)") (class "Default")
      (node (ref "IC24") (pin "3") (pinfunction "ADJ_3") (pintype "input"))
      (node (ref "IC26") (pin "4") (pinfunction "ADJ_4") (pintype "input"))
      (node (ref "R61") (pin "1") (pinfunction "1_1") (pintype "passive"))
      (node (ref "R63") (pin "2") (pinfunction "2_2") (pintype "passive"))
    )
    (net (code "20") (name "Net-(IC24-BYP)") (class "Default")
      (node (ref "C46") (pin "1") (pinfunction "1_1") (pintype "passive"))
      (node (ref "IC24") (pin "5") (pinfunction "BYP_5") (pintype "passive"))
    )
    (net (code "21") (name "Net-(IC25-+Vin)") (class "Default")
      (node (ref "C52") (pin "1") (pinfunction "1_1") (pintype "passive"))
      (node (ref "C53") (pin "2") (pinfunction "2_2") (pintype "passive"))
      (node (ref "C54") (pin "2") (pinfunction "2_2") (pintype "passive"))
      (node (ref "C55") (pin "2") (pinfunction "2_2") (pintype "passive"))
      (node (ref "C56") (pin "2") (pinfunction "2_2") (pintype "passive"))
      (node (ref "C73") (pin "2") (pinfunction "2_2") (pintype "passive"))
      (node (ref "C74") (pin "2") (pinfunction "2_2") (pintype "passive"))
      (node (ref "C85") (pin "2") (pinfunction "2_2") (pintype "passive"))
      (node (ref "C86") (pin "2") (pinfunction "2_2") (pintype "passive"))
      (node (ref "IC25") (pin "1") (pinfunction "+Vin_1") (pintype "power_in"))
      (node (ref "IC28") (pin "2") (pinfunction "VIN_2") (pintype "input"))
      (node (ref "IC31") (pin "2") (pinfunction "VIN_2") (pintype "input"))
      (node (ref "L4") (pin "2") (pinfunction "2_2") (pintype "passive"))
    )
    (net (code "22") (name "Net-(IC25-RC)") (class "Default")
      (node (ref "IC25") (pin "2") (pinfunction "RC_2") (pintype "input"))
      (node (ref "R57") (pin "2") (pinfunction "2_2") (pintype "passive"))
    )
    (net (code "23") (name "Net-(IC25-TRM)") (class "Default")
      (node (ref "IC25") (pin "6") (pinfunction "TRM_6") (pintype "power_in"))
      (node (ref "R56") (pin "1") (pinfunction "1_1") (pintype "passive"))
      (node (ref "R58") (pin "2") (pinfunction "2_2") (pintype "passive"))
    )
    (net (code "24") (name "Net-(IC27A-IN-)") (class "Default")
      (node (ref "IC27") (pin "2") (pinfunction "IN-_2") (pintype "input"))
      (node (ref "R60") (pin "1") (pinfunction "1_1") (pintype "passive"))
    )
    (net (code "25") (name "Net-(IC28-FB)") (class "Default")
      (node (ref "IC28") (pin "5") (pinfunction "FB_5") (pintype "input"))
      (node (ref "R66") (pin "1") (pinfunction "1_1") (pintype "passive"))
      (node (ref "R68") (pin "2") (pinfunction "2_2") (pintype "passive"))
    )
    (net (code "26") (name "Net-(IC28-SW)") (class "Default")
      (node (ref "IC28") (pin "9") (pinfunction "SW_9") (pintype "output"))
      (node (ref "L7") (pin "1") (pinfunction "1_1") (pintype "passive"))
    )
    (net (code "27") (name "Net-(IC29-ADJ)") (class "Default")
      (node (ref "IC29") (pin "4") (pinfunction "ADJ_4") (pintype "input"))
      (node (ref "IC30") (pin "4") (pinfunction "ADJ_4") (pintype "input"))
      (node (ref "R70") (pin "1") (pinfunction "1_1") (pintype "passive"))
      (node (ref "R71") (pin "2") (pinfunction "2_2") (pintype "passive"))
    )
    (net (code "28") (name "Net-(IC30-BYP)") (class "Default")
      (node (ref "C75") (pin "1") (pinfunction "1_1") (pintype "passive"))
      (node (ref "IC30") (pin "3") (pinfunction "BYP_3") (pintype "input"))
    )
    (net (code "29") (name "Net-(IC31-FB)") (class "Default")
      (node (ref "IC31") (pin "5") (pinfunction "FB_5") (pintype "input"))
      (node (ref "R72") (pin "1") (pinfunction "1_1") (pintype "passive"))
      (node (ref "R74") (pin "2") (pinfunction "2_2") (pintype "passive"))
    )
    (net (code "30") (name "Net-(IC31-SW)") (class "Default")
      (node (ref "IC31") (pin "9") (pinfunction "SW_9") (pintype "output"))
      (node (ref "L9") (pin "1") (pinfunction "1_1") (pintype "passive"))
    )
    (net (code "31") (name "Net-(IC32-ADJ)") (class "Default")
      (node (ref "IC32") (pin "2") (pinfunction "ADJ_2") (pintype "input"))
      (node (ref "R73") (pin "1") (pinfunction "1_1") (pintype "passive"))
      (node (ref "R75") (pin "2") (pinfunction "2_2") (pintype "passive"))
    )
    (net (code "32") (name "Net-(IC32-BYP)") (class "Default")
      (node (ref "C82") (pin "1") (pinfunction "1_1") (pintype "passive"))
      (node (ref "IC32") (pin "4") (pinfunction "BYP_4") (pintype "passive"))
    )
    (net (code "33") (name "P2V5A") (class "Default")
      (node (ref "C71") (pin "2") (pinfunction "2_2") (pintype "passive"))
      (node (ref "C75") (pin "2") (pinfunction "2_2") (pintype "passive"))
      (node (ref "C76") (pin "2") (pinfunction "2_2") (pintype "passive"))
      (node (ref "C77") (pin "1") (pinfunction "1_1") (pintype "passive"))
      (node (ref "IC29") (pin "5") (pinfunction "OUT_5") (pintype "power_in"))
      (node (ref "IC30") (pin "5") (pinfunction "OUT_5") (pintype "power_in"))
      (node (ref "R70") (pin "2") (pinfunction "2_2") (pintype "passive"))
      (node (ref "TP10") (pin "1") (pinfunction "1_1") (pintype "bidirectional"))
    )
    (net (code "34") (name "P3V3") (class "Default")
      (node (ref "C69") (pin "2") (pinfunction "2_2") (pintype "passive"))
      (node (ref "C70") (pin "2") (pinfunction "2_2") (pintype "passive"))
      (node (ref "D9") (pin "1") (pinfunction "C_1") (pintype "passive"))
      (node (ref "IC27") (pin "5") (pinfunction "IN+_5") (pintype "input"))
      (node (ref "IC28") (pin "10") (pinfunction "VOS_10") (pintype "input"))
      (node (ref "IC28") (pin "8") (pinfunction "SLEEP_8") (pintype "input"))
      (node (ref "L7") (pin "2") (pinfunction "2_2") (pintype "passive"))
      (node (ref "L8") (pin "1") (pinfunction "1_1") (pintype "passive"))
      (node (ref "R65") (pin "1") (pinfunction "1_1") (pintype "passive"))
      (node (ref "R66") (pin "2") (pinfunction "2_2") (pintype "passive"))
    )
    (net (code "35") (name "P3V3A") (class "Default")
      (node (ref "C67") (pin "1") (pinfunction "1_1") (pintype "passive"))
      (node (ref "C68") (pin "2") (pinfunction "2_2") (pintype "passive"))
      (node (ref "D7") (pin "1") (pinfunction "C_1") (pintype "passive"))
      (node (ref "IC29") (pin "1") (pinfunction "IN_1") (pintype "input"))
      (node (ref "IC29") (pin "3") (pinfunction "~{SHDN}_3") (pintype "input"))
      (node (ref "IC30") (pin "1") (pinfunction "IN_1") (pintype "input"))
      (node (ref "L8") (pin "2") (pinfunction "2_2") (pintype "passive"))
      (node (ref "R60") (pin "2") (pinfunction "2_2") (pintype "passive"))
      (node (ref "TP11") (pin "1") (pinfunction "1_1") (pintype "bidirectional"))
    )
    (net (code "36") (name "P5V0A") (class "Default")
      (node (ref "C82") (pin "2") (pinfunction "2_2") (pintype "passive"))
      (node (ref "C83") (pin "2") (pinfunction "2_2") (pintype "passive"))
      (node (ref "C84") (pin "1") (pinfunction "1_1") (pintype "passive"))
      (node (ref "IC32") (pin "1") (pinfunction "OUT_1") (pintype "power_in"))
      (node (ref "R73") (pin "2") (pinfunction "2_2") (pintype "passive"))
      (node (ref "TP13") (pin "1") (pinfunction "1_1") (pintype "bidirectional"))
    )
    (net (code "37") (name "P6V0") (class "Default")
      (node (ref "C78") (pin "2") (pinfunction "2_2") (pintype "passive"))
      (node (ref "C79") (pin "2") (pinfunction "2_2") (pintype "passive"))
      (node (ref "IC31") (pin "10") (pinfunction "VOS_10") (pintype "input"))
      (node (ref "IC31") (pin "8") (pinfunction "SLEEP_8") (pintype "input"))
      (node (ref "L10") (pin "1") (pinfunction "1_1") (pintype "passive"))
      (node (ref "L9") (pin "2") (pinfunction "2_2") (pintype "passive"))
      (node (ref "R69") (pin "2") (pinfunction "2_2") (pintype "passive"))
      (node (ref "R72") (pin "2") (pinfunction "2_2") (pintype "passive"))
    )
    (net (code "38") (name "P6V0A") (class "Default")
      (node (ref "C80") (pin "1") (pinfunction "1_1") (pintype "passive"))
      (node (ref "C81") (pin "2") (pinfunction "2_2") (pintype "passive"))
      (node (ref "D8") (pin "1") (pinfunction "C_1") (pintype "passive"))
      (node (ref "IC32") (pin "5") (pinfunction "~{SHDN}_5") (pintype "input"))
      (node (ref "IC32") (pin "8") (pinfunction "IN_8") (pintype "input"))
      (node (ref "L10") (pin "2") (pinfunction "2_2") (pintype "passive"))
      (node (ref "R53") (pin "2") (pinfunction "2_2") (pintype "passive"))
      (node (ref "R64") (pin "2") (pinfunction "2_2") (pintype "passive"))
      (node (ref "TP12") (pin "1") (pinfunction "1_1") (pintype "bidirectional"))
    )
    (net (code "39") (name "P12V0") (class "Default")
      (node (ref "C57") (pin "2") (pinfunction "2_2") (pintype "passive"))
      (node (ref "IC27") (pin "8") (pinfunction "V+_8") (pintype "power_in"))
      (node (ref "L4") (pin "1") (pinfunction "1_1") (pintype "passive"))
    )
    (net (code "40") (name "P12V0A") (class "Default")
      (node (ref "C38") (pin "1") (pinfunction "1_1") (pintype "passive"))
      (node (ref "C39") (pin "2") (pinfunction "2_2") (pintype "passive"))
      (node (ref "C40") (pin "2") (pinfunction "2_2") (pintype "passive"))
      (node (ref "D5") (pin "1") (pinfunction "C_1") (pintype "passive"))
      (node (ref "IC21") (pin "1") (pinfunction "OUT_1") (pintype "power_in"))
      (node (ref "R51") (pin "2") (pinfunction "2_2") (pintype "passive"))
      (node (ref "TP7") (pin "1") (pinfunction "1_1") (pintype "bidirectional"))
    )
    (net (code "41") (name "P13V0") (class "Default")
      (node (ref "C37") (pin "2") (pinfunction "2_2") (pintype "passive"))
      (node (ref "C43") (pin "2") (pinfunction "2_2") (pintype "passive"))
      (node (ref "C47") (pin "1") (pinfunction "1_1") (pintype "passive"))
      (node (ref "C51") (pin "2") (pinfunction "2_2") (pintype "passive"))
      (node (ref "IC21") (pin "8") (pinfunction "IN_8") (pintype "input"))
      (node (ref "IC22") (pin "1") (pinfunction "IN_1") (pintype "input"))
      (node (ref "IC22") (pin "3") (pinfunction "~{SHDN}_3") (pintype "input"))
      (node (ref "IC23") (pin "1") (pinfunction "IN_1") (pintype "input"))
      (node (ref "L3") (pin "2") (pinfunction "2_2") (pintype "passive"))
    )
    (net (code "42") (name "P13V0S") (class "Default")
      (node (ref "C48") (pin "2") (pinfunction "2_2") (pintype "passive"))
      (node (ref "IC25") (pin "7") (pinfunction "+Vout_7") (pintype "power_in"))
      (node (ref "L2") (pin "1") (pinfunction "1_1") (pintype "passive"))
      (node (ref "R56") (pin "2") (pinfunction "2_2") (pintype "passive"))
    )
    (net (code "43") (name "REF_P4V096") (class "Default")
      (node (ref "R59") (pin "1") (pinfunction "1_1") (pintype "passive"))
    )
    (net (code "44") (name "REF_VCC") (class "Default")
      (node (ref "C41") (pin "2") (pinfunction "2_2") (pintype "passive"))
      (node (ref "C42") (pin "2") (pinfunction "2_2") (pintype "passive"))
      (node (ref "C44") (pin "1") (pinfunction "1_1") (pintype "passive"))
      (node (ref "C45") (pin "2") (pinfunction "2_2") (pintype "passive"))
      (node (ref "IC22") (pin "5") (pinfunction "OUT_5") (pintype "power_in"))
      (node (ref "IC23") (pin "5") (pinfunction "OUT_5") (pintype "power_in"))
      (node (ref "R54") (pin "2") (pinfunction "2_2") (pintype "passive"))
      (node (ref "TP8") (pin "1") (pinfunction "1_1") (pintype "bidirectional"))
    )
    (net (code "45") (name "unconnected-(IC28-NC-Pad4)") (class "Default")
      (node (ref "IC28") (pin "4") (pinfunction "NC_4") (pintype "passive"))
    )
    (net (code "46") (name "unconnected-(IC31-NC-Pad4)") (class "Default")
      (node (ref "IC31") (pin "4") (pinfunction "NC_4") (pintype "passive"))
    )
  )
)
